# Serial_Header.net
KiCad netlist of a schematic drawn in Altium Designer
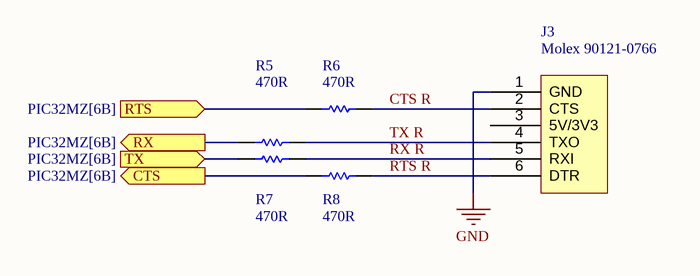
[diagram p0: Serial Header.SchDoc]

(export (version "E")
  (design (tool "Eeschema 10.0.6"))
  (components
    (comp (ref "J3")
      (value "Molex 90121-0766")
      (footprint "Molex 90120-0926")
      (libsource (lib "x-io") (part "FTDI Breakout"))
    )
    (comp (ref "R5") (value "470R") (footprint "Resistor 0402") (libsource (lib "x-io") (part "Resistor")))
    (comp (ref "R6") (value "470R") (footprint "Resistor 0402") (libsource (lib "x-io") (part "Resistor")))
    (comp (ref "R7") (value "470R") (footprint "Resistor 0402") (libsource (lib "x-io") (part "Resistor")))
    (comp (ref "R8") (value "470R") (footprint "Resistor 0402") (libsource (lib "x-io") (part "Resistor")))
  )
  (nets
    (net (code "1") (name "/CTS") (class "Default")
      (node (ref "R8") (pin "2") (pinfunction "2_2") (pintype "passive"))
    )
    (net (code "2") (name "/CTS R") (class "Default")
      (node (ref "J3") (pin "2") (pinfunction "CTS_2") (pintype "passive"))
      (node (ref "R6") (pin "1") (pinfunction "1_1") (pintype "passive"))
    )
    (net (code "3") (name "/RTS") (class "Default")
      (node (ref "R6") (pin "2") (pinfunction "2_2") (pintype "passive"))
    )
    (net (code "4") (name "/RTS R") (class "Default")
      (node (ref "J3") (pin "6") (pinfunction "DTR_6") (pintype "passive"))
      (node (ref "R8") (pin "1") (pinfunction "1_1") (pintype "passive"))
    )
    (net (code "5") (name "/RX") (class "Default")
      (node (ref "R5") (pin "2") (pinfunction "2_2") (pintype "passive"))
    )
    (net (code "6") (name "/RX R") (class "Default")
      (node (ref "J3") (pin "5") (pinfunction "RXI_5") (pintype "passive"))
      (node (ref "R7") (pin "1") (pinfunction "1_1") (pintype "passive"))
    )
    (net (code "7") (name "/TX") (class "Default")
      (node (ref "R7") (pin "2") (pinfunction "2_2") (pintype "passive"))
    )
    (net (code "8") (name "/TX R") (class "Default")
      (node (ref "J3") (pin "4") (pinfunction "TXO_4") (pintype "passive"))
      (node (ref "R5") (pin "1") (pinfunction "1_1") (pintype "passive"))
    )
    (net (code "9") (name "GND") (class "Default")
      (node (ref "J3") (pin "1") (pinfunction "GND_1") (pintype "passive"))
    )
    (net (code "10") (name "unconnected-(J3-5V{slash}3V3-Pad3)") (class "Default")
      (node (ref "J3") (pin "3") (pinfunction "5V/3V3_3") (pintype "passive"))
    )
  )
)
